# WRIST_Sensors.net
KiCad netlist of a schematic drawn in EAGLE
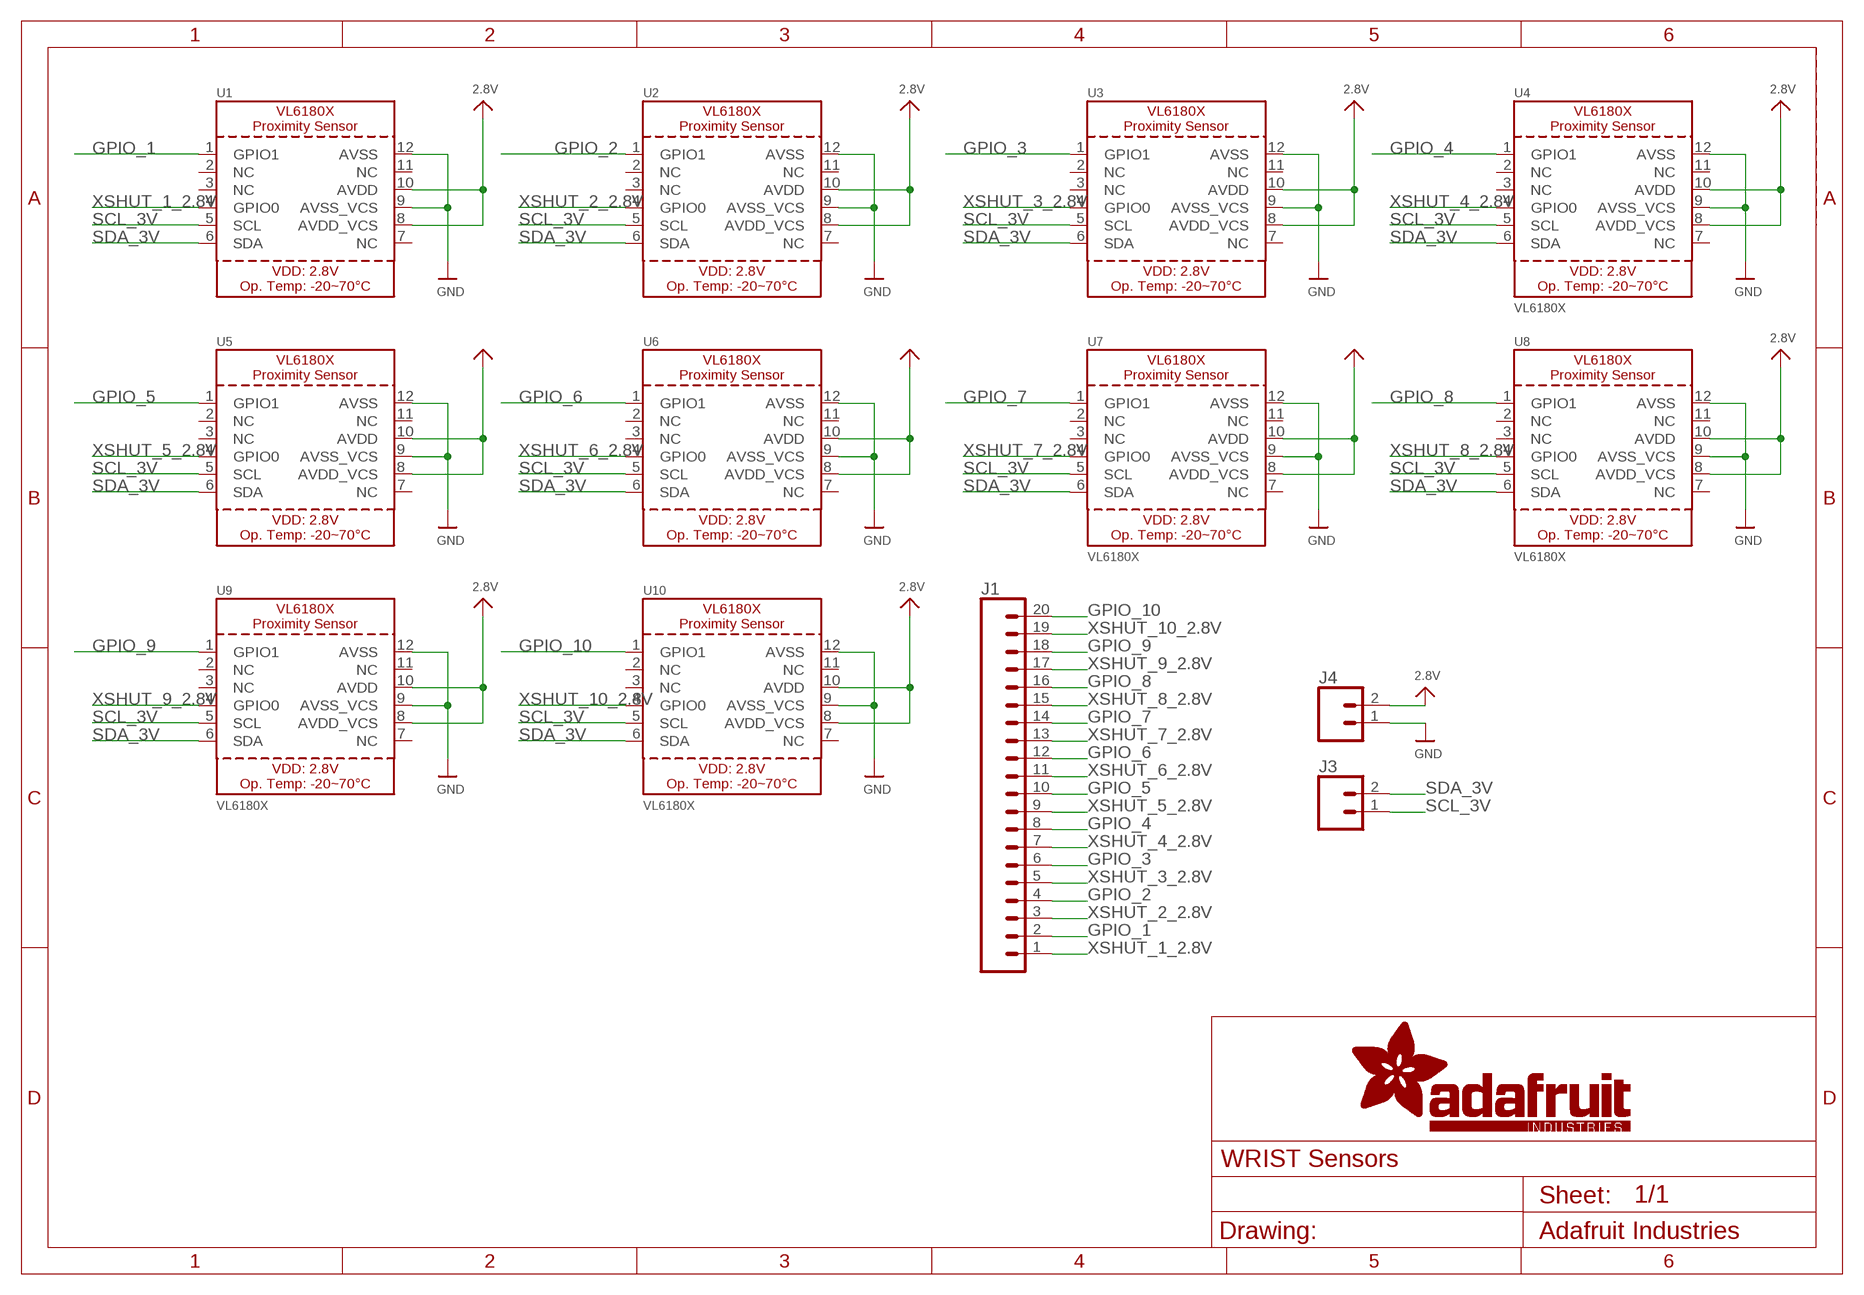
[diagram p0: schematic, sheet 1]

(export (version "E")
  (design (tool "Eeschema 10.0.6"))
  (components
    (comp (ref "J1")
      (value "CONN_20NOSILK")
      (footprint "eagle-import:1X20_NOSILK")
      (libsource (lib "eagle-import") (part "CONN_20NOSILK"))
    )
    (comp (ref "J3")
      (value "CONN_021X02_NO_SILK")
      (footprint "eagle-import:1X02_NO_SILK")
      (libsource (lib "eagle-import") (part "CONN_021X02_NO_SILK"))
    )
    (comp (ref "J4")
      (value "CONN_021X02_NO_SILK")
      (footprint "eagle-import:1X02_NO_SILK")
      (libsource (lib "eagle-import") (part "CONN_021X02_NO_SILK"))
    )
    (comp (ref "U1")
      (value "VL6180X")
      (footprint "eagle-import:VL6180")
      (libsource (lib "eagle-import") (part "VL6180X"))
    )
    (comp (ref "U2")
      (value "VL6180X")
      (footprint "eagle-import:VL6180")
      (libsource (lib "eagle-import") (part "VL6180X"))
    )
    (comp (ref "U3")
      (value "VL6180X")
      (footprint "eagle-import:VL6180")
      (libsource (lib "eagle-import") (part "VL6180X"))
    )
    (comp (ref "U4")
      (value "VL6180X")
      (footprint "eagle-import:VL6180")
      (libsource (lib "eagle-import") (part "VL6180X"))
    )
    (comp (ref "U5")
      (value "VL6180X")
      (footprint "eagle-import:VL6180")
      (libsource (lib "eagle-import") (part "VL6180X"))
    )
    (comp (ref "U6")
      (value "VL6180X")
      (footprint "eagle-import:VL6180")
      (libsource (lib "eagle-import") (part "VL6180X"))
    )
    (comp (ref "U7")
      (value "VL6180X")
      (footprint "eagle-import:VL6180")
      (libsource (lib "eagle-import") (part "VL6180X"))
    )
    (comp (ref "U8")
      (value "VL6180X")
      (footprint "eagle-import:VL6180")
      (libsource (lib "eagle-import") (part "VL6180X"))
    )
    (comp (ref "U9")
      (value "VL6180X")
      (footprint "eagle-import:VL6180")
      (libsource (lib "eagle-import") (part "VL6180X"))
    )
    (comp (ref "U10")
      (value "VL6180X")
      (footprint "eagle-import:VL6180")
      (libsource (lib "eagle-import") (part "VL6180X"))
    )
  )
  (nets
    (net (code "1") (name "/GPIO_1") (class "Default")
      (node (ref "J1") (pin "2") (pinfunction "2_2") (pintype "passive"))
      (node (ref "U1") (pin "1") (pinfunction "GPIO1_1") (pintype "bidirectional"))
    )
    (net (code "2") (name "/GPIO_2") (class "Default")
      (node (ref "J1") (pin "4") (pinfunction "4_4") (pintype "passive"))
      (node (ref "U2") (pin "1") (pinfunction "GPIO1_1") (pintype "bidirectional"))
    )
    (net (code "3") (name "/GPIO_3") (class "Default")
      (node (ref "J1") (pin "6") (pinfunction "6_6") (pintype "passive"))
      (node (ref "U3") (pin "1") (pinfunction "GPIO1_1") (pintype "bidirectional"))
    )
    (net (code "4") (name "/GPIO_4") (class "Default")
      (node (ref "J1") (pin "8") (pinfunction "8_8") (pintype "passive"))
      (node (ref "U4") (pin "1") (pinfunction "GPIO1_1") (pintype "bidirectional"))
    )
    (net (code "5") (name "/GPIO_5") (class "Default")
      (node (ref "J1") (pin "10") (pinfunction "10_10") (pintype "passive"))
      (node (ref "U5") (pin "1") (pinfunction "GPIO1_1") (pintype "bidirectional"))
    )
    (net (code "6") (name "/GPIO_6") (class "Default")
      (node (ref "J1") (pin "12") (pinfunction "12_12") (pintype "passive"))
      (node (ref "U6") (pin "1") (pinfunction "GPIO1_1") (pintype "bidirectional"))
    )
    (net (code "7") (name "/GPIO_7") (class "Default")
      (node (ref "J1") (pin "14") (pinfunction "14_14") (pintype "passive"))
      (node (ref "U7") (pin "1") (pinfunction "GPIO1_1") (pintype "bidirectional"))
    )
    (net (code "8") (name "/GPIO_8") (class "Default")
      (node (ref "J1") (pin "16") (pinfunction "16_16") (pintype "passive"))
      (node (ref "U8") (pin "1") (pinfunction "GPIO1_1") (pintype "bidirectional"))
    )
    (net (code "9") (name "/GPIO_9") (class "Default")
      (node (ref "J1") (pin "18") (pinfunction "18_18") (pintype "passive"))
      (node (ref "U9") (pin "1") (pinfunction "GPIO1_1") (pintype "bidirectional"))
    )
    (net (code "10") (name "/GPIO_10") (class "Default")
      (node (ref "J1") (pin "20") (pinfunction "20_20") (pintype "passive"))
      (node (ref "U10") (pin "1") (pinfunction "GPIO1_1") (pintype "bidirectional"))
    )
    (net (code "11") (name "/SCL_3V") (class "Default")
      (node (ref "J3") (pin "1") (pinfunction "1_1") (pintype "passive"))
      (node (ref "U1") (pin "5") (pinfunction "SCL_5") (pintype "input"))
      (node (ref "U10") (pin "5") (pinfunction "SCL_5") (pintype "input"))
      (node (ref "U2") (pin "5") (pinfunction "SCL_5") (pintype "input"))
      (node (ref "U3") (pin "5") (pinfunction "SCL_5") (pintype "input"))
      (node (ref "U4") (pin "5") (pinfunction "SCL_5") (pintype "input"))
      (node (ref "U5") (pin "5") (pinfunction "SCL_5") (pintype "input"))
      (node (ref "U6") (pin "5") (pinfunction "SCL_5") (pintype "input"))
      (node (ref "U7") (pin "5") (pinfunction "SCL_5") (pintype "input"))
      (node (ref "U8") (pin "5") (pinfunction "SCL_5") (pintype "input"))
      (node (ref "U9") (pin "5") (pinfunction "SCL_5") (pintype "input"))
    )
    (net (code "12") (name "/SDA_3V") (class "Default")
      (node (ref "J3") (pin "2") (pinfunction "2_2") (pintype "passive"))
      (node (ref "U1") (pin "6") (pinfunction "SDA_6") (pintype "bidirectional"))
      (node (ref "U10") (pin "6") (pinfunction "SDA_6") (pintype "bidirectional"))
      (node (ref "U2") (pin "6") (pinfunction "SDA_6") (pintype "bidirectional"))
      (node (ref "U3") (pin "6") (pinfunction "SDA_6") (pintype "bidirectional"))
      (node (ref "U4") (pin "6") (pinfunction "SDA_6") (pintype "bidirectional"))
      (node (ref "U5") (pin "6") (pinfunction "SDA_6") (pintype "bidirectional"))
      (node (ref "U6") (pin "6") (pinfunction "SDA_6") (pintype "bidirectional"))
      (node (ref "U7") (pin "6") (pinfunction "SDA_6") (pintype "bidirectional"))
      (node (ref "U8") (pin "6") (pinfunction "SDA_6") (pintype "bidirectional"))
      (node (ref "U9") (pin "6") (pinfunction "SDA_6") (pintype "bidirectional"))
    )
    (net (code "13") (name "/XSHUT_1_2.8V") (class "Default")
      (node (ref "J1") (pin "1") (pinfunction "1_1") (pintype "passive"))
      (node (ref "U1") (pin "4") (pinfunction "GPIO0_4") (pintype "bidirectional"))
    )
    (net (code "14") (name "/XSHUT_2_2.8V") (class "Default")
      (node (ref "J1") (pin "3") (pinfunction "3_3") (pintype "passive"))
      (node (ref "U2") (pin "4") (pinfunction "GPIO0_4") (pintype "bidirectional"))
    )
    (net (code "15") (name "/XSHUT_3_2.8V") (class "Default")
      (node (ref "J1") (pin "5") (pinfunction "5_5") (pintype "passive"))
      (node (ref "U3") (pin "4") (pinfunction "GPIO0_4") (pintype "bidirectional"))
    )
    (net (code "16") (name "/XSHUT_4_2.8V") (class "Default")
      (node (ref "J1") (pin "7") (pinfunction "7_7") (pintype "passive"))
      (node (ref "U4") (pin "4") (pinfunction "GPIO0_4") (pintype "bidirectional"))
    )
    (net (code "17") (name "/XSHUT_5_2.8V") (class "Default")
      (node (ref "J1") (pin "9") (pinfunction "9_9") (pintype "passive"))
      (node (ref "U5") (pin "4") (pinfunction "GPIO0_4") (pintype "bidirectional"))
    )
    (net (code "18") (name "/XSHUT_6_2.8V") (class "Default")
      (node (ref "J1") (pin "11") (pinfunction "11_11") (pintype "passive"))
      (node (ref "U6") (pin "4") (pinfunction "GPIO0_4") (pintype "bidirectional"))
    )
    (net (code "19") (name "/XSHUT_7_2.8V") (class "Default")
      (node (ref "J1") (pin "13") (pinfunction "13_13") (pintype "passive"))
      (node (ref "U7") (pin "4") (pinfunction "GPIO0_4") (pintype "bidirectional"))
    )
    (net (code "20") (name "/XSHUT_8_2.8V") (class "Default")
      (node (ref "J1") (pin "15") (pinfunction "15_15") (pintype "passive"))
      (node (ref "U8") (pin "4") (pinfunction "GPIO0_4") (pintype "bidirectional"))
    )
    (net (code "21") (name "/XSHUT_9_2.8V") (class "Default")
      (node (ref "J1") (pin "17") (pinfunction "17_17") (pintype "passive"))
      (node (ref "U9") (pin "4") (pinfunction "GPIO0_4") (pintype "bidirectional"))
    )
    (net (code "22") (name "/XSHUT_10_2.8V") (class "Default")
      (node (ref "J1") (pin "19") (pinfunction "19_19") (pintype "passive"))
      (node (ref "U10") (pin "4") (pinfunction "GPIO0_4") (pintype "bidirectional"))
    )
    (net (code "23") (name "2.8V") (class "Default")
      (node (ref "J4") (pin "2") (pinfunction "2_2") (pintype "passive"))
      (node (ref "U1") (pin "10") (pinfunction "AVDD_10") (pintype "power_in"))
      (node (ref "U1") (pin "8") (pinfunction "AVDD_VCS_8") (pintype "power_in"))
      (node (ref "U10") (pin "10") (pinfunction "AVDD_10") (pintype "power_in"))
      (node (ref "U10") (pin "8") (pinfunction "AVDD_VCS_8") (pintype "power_in"))
      (node (ref "U2") (pin "10") (pinfunction "AVDD_10") (pintype "power_in"))
      (node (ref "U2") (pin "8") (pinfunction "AVDD_VCS_8") (pintype "power_in"))
      (node (ref "U3") (pin "10") (pinfunction "AVDD_10") (pintype "power_in"))
      (node (ref "U3") (pin "8") (pinfunction "AVDD_VCS_8") (pintype "power_in"))
      (node (ref "U4") (pin "10") (pinfunction "AVDD_10") (pintype "power_in"))
      (node (ref "U4") (pin "8") (pinfunction "AVDD_VCS_8") (pintype "power_in"))
      (node (ref "U5") (pin "10") (pinfunction "AVDD_10") (pintype "power_in"))
      (node (ref "U5") (pin "8") (pinfunction "AVDD_VCS_8") (pintype "power_in"))
      (node (ref "U6") (pin "10") (pinfunction "AVDD_10") (pintype "power_in"))
      (node (ref "U6") (pin "8") (pinfunction "AVDD_VCS_8") (pintype "power_in"))
      (node (ref "U7") (pin "10") (pinfunction "AVDD_10") (pintype "power_in"))
      (node (ref "U7") (pin "8") (pinfunction "AVDD_VCS_8") (pintype "power_in"))
      (node (ref "U8") (pin "10") (pinfunction "AVDD_10") (pintype "power_in"))
      (node (ref "U8") (pin "8") (pinfunction "AVDD_VCS_8") (pintype "power_in"))
      (node (ref "U9") (pin "10") (pinfunction "AVDD_10") (pintype "power_in"))
      (node (ref "U9") (pin "8") (pinfunction "AVDD_VCS_8") (pintype "power_in"))
    )
    (net (code "24") (name "GND") (class "Default")
      (node (ref "J4") (pin "1") (pinfunction "1_1") (pintype "passive"))
      (node (ref "U1") (pin "12") (pinfunction "AVSS_12") (pintype "power_in"))
      (node (ref "U1") (pin "9") (pinfunction "AVSS_VCS_9") (pintype "power_in"))
      (node (ref "U10") (pin "12") (pinfunction "AVSS_12") (pintype "power_in"))
      (node (ref "U10") (pin "9") (pinfunction "AVSS_VCS_9") (pintype "power_in"))
      (node (ref "U2") (pin "12") (pinfunction "AVSS_12") (pintype "power_in"))
      (node (ref "U2") (pin "9") (pinfunction "AVSS_VCS_9") (pintype "power_in"))
      (node (ref "U3") (pin "12") (pinfunction "AVSS_12") (pintype "power_in"))
      (node (ref "U3") (pin "9") (pinfunction "AVSS_VCS_9") (pintype "power_in"))
      (node (ref "U4") (pin "12") (pinfunction "AVSS_12") (pintype "power_in"))
      (node (ref "U4") (pin "9") (pinfunction "AVSS_VCS_9") (pintype "power_in"))
      (node (ref "U5") (pin "12") (pinfunction "AVSS_12") (pintype "power_in"))
      (node (ref "U5") (pin "9") (pinfunction "AVSS_VCS_9") (pintype "power_in"))
      (node (ref "U6") (pin "12") (pinfunction "AVSS_12") (pintype "power_in"))
      (node (ref "U6") (pin "9") (pinfunction "AVSS_VCS_9") (pintype "power_in"))
      (node (ref "U7") (pin "12") (pinfunction "AVSS_12") (pintype "power_in"))
      (node (ref "U7") (pin "9") (pinfunction "AVSS_VCS_9") (pintype "power_in"))
      (node (ref "U8") (pin "12") (pinfunction "AVSS_12") (pintype "power_in"))
      (node (ref "U8") (pin "9") (pinfunction "AVSS_VCS_9") (pintype "power_in"))
      (node (ref "U9") (pin "12") (pinfunction "AVSS_12") (pintype "power_in"))
      (node (ref "U9") (pin "9") (pinfunction "AVSS_VCS_9") (pintype "power_in"))
    )
    (net (code "25") (name "unconnected-(U1-NC-Pad2)") (class "Default")
      (node (ref "U1") (pin "2") (pinfunction "NC_2") (pintype "no_connect"))
    )
    (net (code "26") (name "unconnected-(U1-NC-Pad3)") (class "Default")
      (node (ref "U1") (pin "3") (pinfunction "NC_3") (pintype "no_connect"))
    )
    (net (code "27") (name "unconnected-(U1-NC-Pad7)") (class "Default")
      (node (ref "U1") (pin "7") (pinfunction "NC_7") (pintype "no_connect"))
    )
    (net (code "28") (name "unconnected-(U1-NC-Pad11)") (class "Default")
      (node (ref "U1") (pin "11") (pinfunction "NC_11") (pintype "no_connect"))
    )
    (net (code "29") (name "unconnected-(U2-NC-Pad2)") (class "Default")
      (node (ref "U2") (pin "2") (pinfunction "NC_2") (pintype "no_connect"))
    )
    (net (code "30") (name "unconnected-(U2-NC-Pad3)") (class "Default")
      (node (ref "U2") (pin "3") (pinfunction "NC_3") (pintype "no_connect"))
    )
    (net (code "31") (name "unconnected-(U2-NC-Pad7)") (class "Default")
      (node (ref "U2") (pin "7") (pinfunction "NC_7") (pintype "no_connect"))
    )
    (net (code "32") (name "unconnected-(U2-NC-Pad11)") (class "Default")
      (node (ref "U2") (pin "11") (pinfunction "NC_11") (pintype "no_connect"))
    )
    (net (code "33") (name "unconnected-(U3-NC-Pad2)") (class "Default")
      (node (ref "U3") (pin "2") (pinfunction "NC_2") (pintype "no_connect"))
    )
    (net (code "34") (name "unconnected-(U3-NC-Pad3)") (class "Default")
      (node (ref "U3") (pin "3") (pinfunction "NC_3") (pintype "no_connect"))
    )
    (net (code "35") (name "unconnected-(U3-NC-Pad7)") (class "Default")
      (node (ref "U3") (pin "7") (pinfunction "NC_7") (pintype "no_connect"))
    )
    (net (code "36") (name "unconnected-(U3-NC-Pad11)") (class "Default")
      (node (ref "U3") (pin "11") (pinfunction "NC_11") (pintype "no_connect"))
    )
    (net (code "37") (name "unconnected-(U4-NC-Pad2)") (class "Default")
      (node (ref "U4") (pin "2") (pinfunction "NC_2") (pintype "no_connect"))
    )
    (net (code "38") (name "unconnected-(U4-NC-Pad3)") (class "Default")
      (node (ref "U4") (pin "3") (pinfunction "NC_3") (pintype "no_connect"))
    )
    (net (code "39") (name "unconnected-(U4-NC-Pad7)") (class "Default")
      (node (ref "U4") (pin "7") (pinfunction "NC_7") (pintype "no_connect"))
    )
    (net (code "40") (name "unconnected-(U4-NC-Pad11)") (class "Default")
      (node (ref "U4") (pin "11") (pinfunction "NC_11") (pintype "no_connect"))
    )
    (net (code "41") (name "unconnected-(U5-NC-Pad2)") (class "Default")
      (node (ref "U5") (pin "2") (pinfunction "NC_2") (pintype "no_connect"))
    )
    (net (code "42") (name "unconnected-(U5-NC-Pad3)") (class "Default")
      (node (ref "U5") (pin "3") (pinfunction "NC_3") (pintype "no_connect"))
    )
    (net (code "43") (name "unconnected-(U5-NC-Pad7)") (class "Default")
      (node (ref "U5") (pin "7") (pinfunction "NC_7") (pintype "no_connect"))
    )
    (net (code "44") (name "unconnected-(U5-NC-Pad11)") (class "Default")
      (node (ref "U5") (pin "11") (pinfunction "NC_11") (pintype "no_connect"))
    )
    (net (code "45") (name "unconnected-(U6-NC-Pad2)") (class "Default")
      (node (ref "U6") (pin "2") (pinfunction "NC_2") (pintype "no_connect"))
    )
    (net (code "46") (name "unconnected-(U6-NC-Pad3)") (class "Default")
      (node (ref "U6") (pin "3") (pinfunction "NC_3") (pintype "no_connect"))
    )
    (net (code "47") (name "unconnected-(U6-NC-Pad7)") (class "Default")
      (node (ref "U6") (pin "7") (pinfunction "NC_7") (pintype "no_connect"))
    )
    (net (code "48") (name "unconnected-(U6-NC-Pad11)") (class "Default")
      (node (ref "U6") (pin "11") (pinfunction "NC_11") (pintype "no_connect"))
    )
    (net (code "49") (name "unconnected-(U7-NC-Pad2)") (class "Default")
      (node (ref "U7") (pin "2") (pinfunction "NC_2") (pintype "no_connect"))
    )
    (net (code "50") (name "unconnected-(U7-NC-Pad3)") (class "Default")
      (node (ref "U7") (pin "3") (pinfunction "NC_3") (pintype "no_connect"))
    )
    (net (code "51") (name "unconnected-(U7-NC-Pad7)") (class "Default")
      (node (ref "U7") (pin "7") (pinfunction "NC_7") (pintype "no_connect"))
    )
    (net (code "52") (name "unconnected-(U7-NC-Pad11)") (class "Default")
      (node (ref "U7") (pin "11") (pinfunction "NC_11") (pintype "no_connect"))
    )
    (net (code "53") (name "unconnected-(U8-NC-Pad2)") (class "Default")
      (node (ref "U8") (pin "2") (pinfunction "NC_2") (pintype "no_connect"))
    )
    (net (code "54") (name "unconnected-(U8-NC-Pad3)") (class "Default")
      (node (ref "U8") (pin "3") (pinfunction "NC_3") (pintype "no_connect"))
    )
    (net (code "55") (name "unconnected-(U8-NC-Pad7)") (class "Default")
      (node (ref "U8") (pin "7") (pinfunction "NC_7") (pintype "no_connect"))
    )
    (net (code "56") (name "unconnected-(U8-NC-Pad11)") (class "Default")
      (node (ref "U8") (pin "11") (pinfunction "NC_11") (pintype "no_connect"))
    )
    (net (code "57") (name "unconnected-(U9-NC-Pad2)") (class "Default")
      (node (ref "U9") (pin "2") (pinfunction "NC_2") (pintype "no_connect"))
    )
    (net (code "58") (name "unconnected-(U9-NC-Pad3)") (class "Default")
      (node (ref "U9") (pin "3") (pinfunction "NC_3") (pintype "no_connect"))
    )
    (net (code "59") (name "unconnected-(U9-NC-Pad7)") (class "Default")
      (node (ref "U9") (pin "7") (pinfunction "NC_7") (pintype "no_connect"))
    )
    (net (code "60") (name "unconnected-(U9-NC-Pad11)") (class "Default")
      (node (ref "U9") (pin "11") (pinfunction "NC_11") (pintype "no_connect"))
    )
    (net (code "61") (name "unconnected-(U10-NC-Pad2)") (class "Default")
      (node (ref "U10") (pin "2") (pinfunction "NC_2") (pintype "no_connect"))
    )
    (net (code "62") (name "unconnected-(U10-NC-Pad3)") (class "Default")
      (node (ref "U10") (pin "3") (pinfunction "NC_3") (pintype "no_connect"))
    )
    (net (code "63") (name "unconnected-(U10-NC-Pad7)") (class "Default")
      (node (ref "U10") (pin "7") (pinfunction "NC_7") (pintype "no_connect"))
    )
    (net (code "64") (name "unconnected-(U10-NC-Pad11)") (class "Default")
      (node (ref "U10") (pin "11") (pinfunction "NC_11") (pintype "no_connect"))
    )
  )
)
